# led.net
KiCad netlist of a schematic drawn in EAGLE
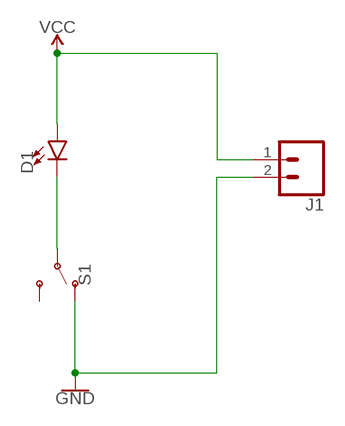
[diagram p0: schematic, sheet 1]

(export (version "E")
  (design (tool "Eeschema 10.0.6"))
  (components
    (comp (ref "D1")
      (value "LED5MM")
      (footprint "eagle-import:LED_5MM")
      (libsource (lib "eagle-import") (part "LED5MM"))
    )
    (comp (ref "J1")
      (value "CONN_02LOCK")
      (footprint "eagle-import:1X02_LOCK")
      (libsource (lib "eagle-import") (part "CONN_02LOCK"))
    )
    (comp (ref "S1")
      (value "SWITCH-SPDT-PTH-11.6X4.0MM-LOCK")
      (footprint "eagle-import:SWITCH_SPDT_PTH_11.6X4.0MM_LOCK")
      (libsource (lib "eagle-import") (part "SWITCH-SPDT-PTH-11.6X4.0MM-LOCK"))
    )
  )
  (nets
    (net (code "1") (name "GND") (class "Default")
      (node (ref "J1") (pin "2") (pinfunction "2_2") (pintype "passive"))
      (node (ref "S1") (pin "1") (pinfunction "O_1") (pintype "passive"))
    )
    (net (code "2") (name "Net-(D1-C)") (class "Default")
      (node (ref "D1") (pin "K") (pinfunction "C_K") (pintype "passive"))
      (node (ref "S1") (pin "2") (pinfunction "P_2") (pintype "passive"))
    )
    (net (code "3") (name "VCC") (class "Default")
      (node (ref "D1") (pin "A") (pinfunction "A_A") (pintype "passive"))
      (node (ref "J1") (pin "1") (pinfunction "1_1") (pintype "passive"))
    )
    (net (code "4") (name "unconnected-(S1-S-Pad3)") (class "Default")
      (node (ref "S1") (pin "3") (pinfunction "S_3") (pintype "passive"))
    )
  )
)
